# Signal_conditioning.net
KiCad netlist of a schematic drawn in Altium Designer
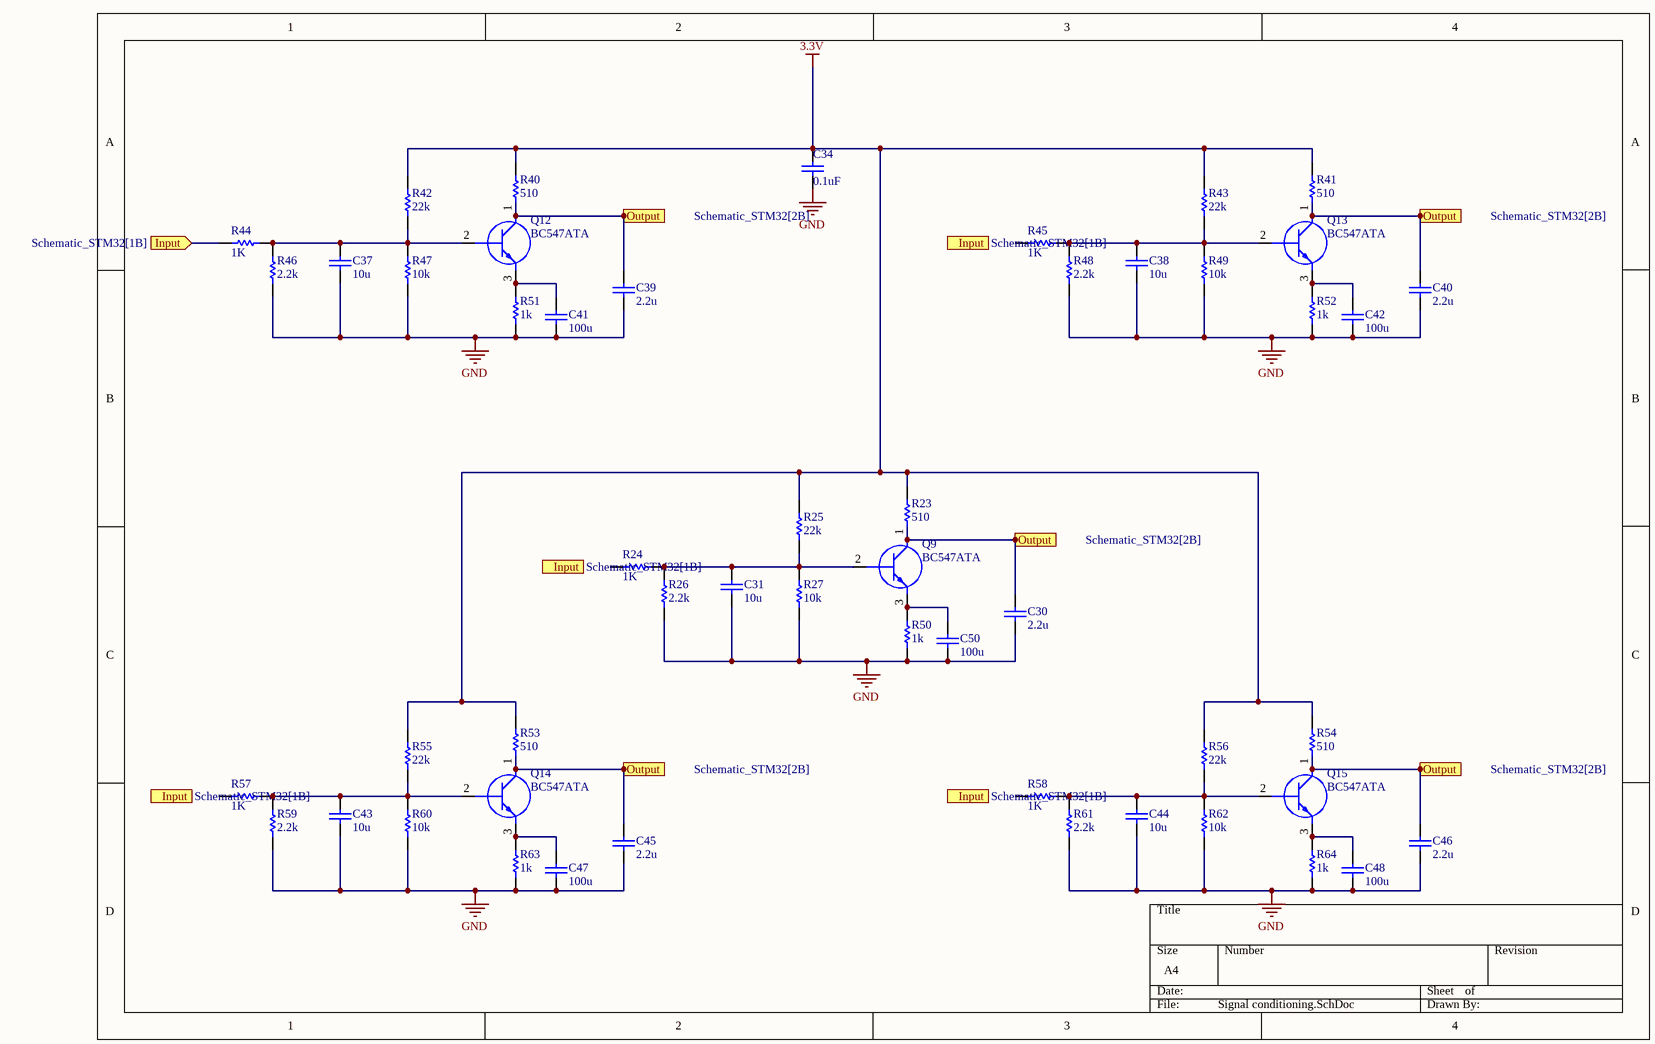
[diagram p0: Signal conditioning.SchDoc]

(export (version "E")
  (design (tool "Eeschema 10.0.6"))
  (components
    (comp (ref "C30")
      (value "2.2u")
      (description "Capacitor")
      (libsource (lib "Simulation Generic Components") (part "Capacitor"))
    )
    (comp (ref "C31")
      (value "10u")
      (description "Capacitor")
      (libsource (lib "Simulation Generic Components") (part "Capacitor"))
    )
    (comp (ref "C34")
      (value "0.1uF")
      (footprint "RAD-0.3")
      (description "Capacitor")
      (fields (field (name "Comment") "Cap") (field (name "PUBLISHER") "Altium Limited"))
      (libsource (lib "Miscellaneous Devices") (part "Cap"))
    )
    (comp (ref "C37")
      (value "10u")
      (description "Capacitor")
      (libsource (lib "Simulation Generic Components") (part "Capacitor"))
    )
    (comp (ref "C38")
      (value "10u")
      (description "Capacitor")
      (libsource (lib "Simulation Generic Components") (part "Capacitor"))
    )
    (comp (ref "C39")
      (value "2.2u")
      (description "Capacitor")
      (libsource (lib "Simulation Generic Components") (part "Capacitor"))
    )
    (comp (ref "C40")
      (value "2.2u")
      (description "Capacitor")
      (libsource (lib "Simulation Generic Components") (part "Capacitor"))
    )
    (comp (ref "C41")
      (value "100u")
      (description "Capacitor")
      (libsource (lib "Simulation Generic Components") (part "Capacitor"))
    )
    (comp (ref "C42")
      (value "100u")
      (description "Capacitor")
      (libsource (lib "Simulation Generic Components") (part "Capacitor"))
    )
    (comp (ref "C43")
      (value "10u")
      (description "Capacitor")
      (libsource (lib "Simulation Generic Components") (part "Capacitor"))
    )
    (comp (ref "C44")
      (value "10u")
      (description "Capacitor")
      (libsource (lib "Simulation Generic Components") (part "Capacitor"))
    )
    (comp (ref "C45")
      (value "2.2u")
      (description "Capacitor")
      (libsource (lib "Simulation Generic Components") (part "Capacitor"))
    )
    (comp (ref "C46")
      (value "2.2u")
      (description "Capacitor")
      (libsource (lib "Simulation Generic Components") (part "Capacitor"))
    )
    (comp (ref "C47")
      (value "100u")
      (description "Capacitor")
      (libsource (lib "Simulation Generic Components") (part "Capacitor"))
    )
    (comp (ref "C48")
      (value "100u")
      (description "Capacitor")
      (libsource (lib "Simulation Generic Components") (part "Capacitor"))
    )
    (comp (ref "C50")
      (value "100u")
      (description "Capacitor")
      (libsource (lib "Simulation Generic Components") (part "Capacitor"))
    )
    (comp (ref "Q9")
      (value "BC547ATA")
      (footprint "SamacSys:TO-92_(TO-226)")
      (description "Transistor BJT NPN")
      (fields (field (name "MOUSER PART NUMBER") "512-BC547ATA"))
      (libsource (lib "*") (part "BC547ATA"))
    )
    (comp (ref "Q12")
      (value "BC547ATA")
      (footprint "SamacSys:TO-92_(TO-226)")
      (description "Transistor BJT NPN")
      (fields (field (name "MOUSER PART NUMBER") "512-BC547ATA"))
      (libsource (lib "*") (part "BC547ATA"))
    )
    (comp (ref "Q13")
      (value "BC547ATA")
      (footprint "SamacSys:TO-92_(TO-226)")
      (description "Transistor BJT NPN")
      (fields (field (name "MOUSER PART NUMBER") "512-BC547ATA"))
      (libsource (lib "*") (part "BC547ATA"))
    )
    (comp (ref "Q14")
      (value "BC547ATA")
      (footprint "SamacSys:TO-92_(TO-226)")
      (description "Transistor BJT NPN")
      (fields (field (name "MOUSER PART NUMBER") "512-BC547ATA"))
      (libsource (lib "*") (part "BC547ATA"))
    )
    (comp (ref "Q15")
      (value "BC547ATA")
      (footprint "SamacSys:TO-92_(TO-226)")
      (description "Transistor BJT NPN")
      (fields (field (name "MOUSER PART NUMBER") "512-BC547ATA"))
      (libsource (lib "*") (part "BC547ATA"))
    )
    (comp (ref "R23")
      (value "510")
      (description "Resistor")
      (libsource (lib "Simulation Generic Components") (part "Resistor"))
    )
    (comp (ref "R24")
      (value "1K")
      (description "Resistor")
      (libsource (lib "Simulation Generic Components") (part "Resistor"))
    )
    (comp (ref "R25")
      (value "22k")
      (description "Resistor")
      (libsource (lib "Simulation Generic Components") (part "Resistor"))
    )
    (comp (ref "R26")
      (value "2.2k")
      (description "Resistor")
      (libsource (lib "Simulation Generic Components") (part "Resistor"))
    )
    (comp (ref "R27")
      (value "10k")
      (description "Resistor")
      (libsource (lib "Simulation Generic Components") (part "Resistor"))
    )
    (comp (ref "R40")
      (value "510")
      (description "Resistor")
      (libsource (lib "Simulation Generic Components") (part "Resistor"))
    )
    (comp (ref "R41")
      (value "510")
      (description "Resistor")
      (libsource (lib "Simulation Generic Components") (part "Resistor"))
    )
    (comp (ref "R42")
      (value "22k")
      (description "Resistor")
      (libsource (lib "Simulation Generic Components") (part "Resistor"))
    )
    (comp (ref "R43")
      (value "22k")
      (description "Resistor")
      (libsource (lib "Simulation Generic Components") (part "Resistor"))
    )
    (comp (ref "R44")
      (value "1K")
      (description "Resistor")
      (libsource (lib "Simulation Generic Components") (part "Resistor"))
    )
    (comp (ref "R45")
      (value "1K")
      (description "Resistor")
      (libsource (lib "Simulation Generic Components") (part "Resistor"))
    )
    (comp (ref "R46")
      (value "2.2k")
      (description "Resistor")
      (libsource (lib "Simulation Generic Components") (part "Resistor"))
    )
    (comp (ref "R47")
      (value "10k")
      (description "Resistor")
      (libsource (lib "Simulation Generic Components") (part "Resistor"))
    )
    (comp (ref "R48")
      (value "2.2k")
      (description "Resistor")
      (libsource (lib "Simulation Generic Components") (part "Resistor"))
    )
    (comp (ref "R49")
      (value "10k")
      (description "Resistor")
      (libsource (lib "Simulation Generic Components") (part "Resistor"))
    )
    (comp (ref "R50")
      (value "1k")
      (description "Resistor")
      (libsource (lib "Simulation Generic Components") (part "Resistor"))
    )
    (comp (ref "R51")
      (value "1k")
      (description "Resistor")
      (libsource (lib "Simulation Generic Components") (part "Resistor"))
    )
    (comp (ref "R52")
      (value "1k")
      (description "Resistor")
      (libsource (lib "Simulation Generic Components") (part "Resistor"))
    )
    (comp (ref "R53")
      (value "510")
      (description "Resistor")
      (libsource (lib "Simulation Generic Components") (part "Resistor"))
    )
    (comp (ref "R54")
      (value "510")
      (description "Resistor")
      (libsource (lib "Simulation Generic Components") (part "Resistor"))
    )
    (comp (ref "R55")
      (value "22k")
      (description "Resistor")
      (libsource (lib "Simulation Generic Components") (part "Resistor"))
    )
    (comp (ref "R56")
      (value "22k")
      (description "Resistor")
      (libsource (lib "Simulation Generic Components") (part "Resistor"))
    )
    (comp (ref "R57")
      (value "1K")
      (description "Resistor")
      (libsource (lib "Simulation Generic Components") (part "Resistor"))
    )
    (comp (ref "R58")
      (value "1K")
      (description "Resistor")
      (libsource (lib "Simulation Generic Components") (part "Resistor"))
    )
    (comp (ref "R59")
      (value "2.2k")
      (description "Resistor")
      (libsource (lib "Simulation Generic Components") (part "Resistor"))
    )
    (comp (ref "R60")
      (value "10k")
      (description "Resistor")
      (libsource (lib "Simulation Generic Components") (part "Resistor"))
    )
    (comp (ref "R61")
      (value "2.2k")
      (description "Resistor")
      (libsource (lib "Simulation Generic Components") (part "Resistor"))
    )
    (comp (ref "R62")
      (value "10k")
      (description "Resistor")
      (libsource (lib "Simulation Generic Components") (part "Resistor"))
    )
    (comp (ref "R63")
      (value "1k")
      (description "Resistor")
      (libsource (lib "Simulation Generic Components") (part "Resistor"))
    )
    (comp (ref "R64")
      (value "1k")
      (description "Resistor")
      (libsource (lib "Simulation Generic Components") (part "Resistor"))
    )
  )
  (nets
    (net (code "1") (name "/Input") (class "Default")
      (node (ref "R44") (pin "1") (pinfunction "1_1") (pintype "passive"))
    )
    (net (code "2") (name "/Output") (class "Default")
      (node (ref "C30") (pin "1") (pinfunction "1_1") (pintype "passive"))
      (node (ref "C39") (pin "1") (pinfunction "1_1") (pintype "passive"))
      (node (ref "C40") (pin "1") (pinfunction "1_1") (pintype "passive"))
      (node (ref "C45") (pin "1") (pinfunction "1_1") (pintype "passive"))
      (node (ref "C46") (pin "1") (pinfunction "1_1") (pintype "passive"))
      (node (ref "Q12") (pin "1") (pinfunction "C_1") (pintype "passive"))
      (node (ref "Q13") (pin "1") (pinfunction "C_1") (pintype "passive"))
      (node (ref "Q14") (pin "1") (pinfunction "C_1") (pintype "passive"))
      (node (ref "Q15") (pin "1") (pinfunction "C_1") (pintype "passive"))
      (node (ref "Q9") (pin "1") (pinfunction "C_1") (pintype "passive"))
      (node (ref "R23") (pin "1") (pinfunction "1_1") (pintype "passive"))
      (node (ref "R40") (pin "1") (pinfunction "1_1") (pintype "passive"))
      (node (ref "R41") (pin "1") (pinfunction "1_1") (pintype "passive"))
      (node (ref "R53") (pin "1") (pinfunction "1_1") (pintype "passive"))
      (node (ref "R54") (pin "1") (pinfunction "1_1") (pintype "passive"))
    )
    (net (code "3") (name "3.3V") (class "Default")
      (node (ref "C34") (pin "2") (pinfunction "2_2") (pintype "passive"))
      (node (ref "R23") (pin "2") (pinfunction "2_2") (pintype "passive"))
      (node (ref "R25") (pin "2") (pinfunction "2_2") (pintype "passive"))
      (node (ref "R40") (pin "2") (pinfunction "2_2") (pintype "passive"))
      (node (ref "R41") (pin "2") (pinfunction "2_2") (pintype "passive"))
      (node (ref "R42") (pin "2") (pinfunction "2_2") (pintype "passive"))
      (node (ref "R43") (pin "2") (pinfunction "2_2") (pintype "passive"))
      (node (ref "R53") (pin "2") (pinfunction "2_2") (pintype "passive"))
      (node (ref "R54") (pin "2") (pinfunction "2_2") (pintype "passive"))
      (node (ref "R55") (pin "2") (pinfunction "2_2") (pintype "passive"))
      (node (ref "R56") (pin "2") (pinfunction "2_2") (pintype "passive"))
    )
    (net (code "4") (name "GND") (class "Default")
      (node (ref "C30") (pin "2") (pinfunction "2_2") (pintype "passive"))
      (node (ref "C31") (pin "2") (pinfunction "2_2") (pintype "passive"))
      (node (ref "C34") (pin "1") (pinfunction "1_1") (pintype "passive"))
      (node (ref "C37") (pin "2") (pinfunction "2_2") (pintype "passive"))
      (node (ref "C38") (pin "2") (pinfunction "2_2") (pintype "passive"))
      (node (ref "C39") (pin "2") (pinfunction "2_2") (pintype "passive"))
      (node (ref "C40") (pin "2") (pinfunction "2_2") (pintype "passive"))
      (node (ref "C41") (pin "1") (pinfunction "1_1") (pintype "passive"))
      (node (ref "C42") (pin "1") (pinfunction "1_1") (pintype "passive"))
      (node (ref "C43") (pin "2") (pinfunction "2_2") (pintype "passive"))
      (node (ref "C44") (pin "2") (pinfunction "2_2") (pintype "passive"))
      (node (ref "C45") (pin "2") (pinfunction "2_2") (pintype "passive"))
      (node (ref "C46") (pin "2") (pinfunction "2_2") (pintype "passive"))
      (node (ref "C47") (pin "1") (pinfunction "1_1") (pintype "passive"))
      (node (ref "C48") (pin "1") (pinfunction "1_1") (pintype "passive"))
      (node (ref "C50") (pin "1") (pinfunction "1_1") (pintype "passive"))
      (node (ref "R26") (pin "1") (pinfunction "1_1") (pintype "passive"))
      (node (ref "R27") (pin "1") (pinfunction "1_1") (pintype "passive"))
      (node (ref "R46") (pin "1") (pinfunction "1_1") (pintype "passive"))
      (node (ref "R47") (pin "1") (pinfunction "1_1") (pintype "passive"))
      (node (ref "R48") (pin "1") (pinfunction "1_1") (pintype "passive"))
      (node (ref "R49") (pin "1") (pinfunction "1_1") (pintype "passive"))
      (node (ref "R50") (pin "1") (pinfunction "1_1") (pintype "passive"))
      (node (ref "R51") (pin "1") (pinfunction "1_1") (pintype "passive"))
      (node (ref "R52") (pin "1") (pinfunction "1_1") (pintype "passive"))
      (node (ref "R59") (pin "1") (pinfunction "1_1") (pintype "passive"))
      (node (ref "R60") (pin "1") (pinfunction "1_1") (pintype "passive"))
      (node (ref "R61") (pin "1") (pinfunction "1_1") (pintype "passive"))
      (node (ref "R62") (pin "1") (pinfunction "1_1") (pintype "passive"))
      (node (ref "R63") (pin "1") (pinfunction "1_1") (pintype "passive"))
      (node (ref "R64") (pin "1") (pinfunction "1_1") (pintype "passive"))
    )
    (net (code "5") (name "Net-(Q9-B)") (class "Default")
      (node (ref "C31") (pin "1") (pinfunction "1_1") (pintype "passive"))
      (node (ref "Q9") (pin "2") (pinfunction "B_2") (pintype "passive"))
      (node (ref "R24") (pin "2") (pinfunction "2_2") (pintype "passive"))
      (node (ref "R25") (pin "1") (pinfunction "1_1") (pintype "passive"))
      (node (ref "R26") (pin "2") (pinfunction "2_2") (pintype "passive"))
      (node (ref "R27") (pin "2") (pinfunction "2_2") (pintype "passive"))
    )
    (net (code "6") (name "Net-(Q9-E)") (class "Default")
      (node (ref "C50") (pin "2") (pinfunction "2_2") (pintype "passive"))
      (node (ref "Q9") (pin "3") (pinfunction "E_3") (pintype "passive"))
      (node (ref "R50") (pin "2") (pinfunction "2_2") (pintype "passive"))
    )
    (net (code "7") (name "Net-(Q12-B)") (class "Default")
      (node (ref "C37") (pin "1") (pinfunction "1_1") (pintype "passive"))
      (node (ref "Q12") (pin "2") (pinfunction "B_2") (pintype "passive"))
      (node (ref "R42") (pin "1") (pinfunction "1_1") (pintype "passive"))
      (node (ref "R44") (pin "2") (pinfunction "2_2") (pintype "passive"))
      (node (ref "R46") (pin "2") (pinfunction "2_2") (pintype "passive"))
      (node (ref "R47") (pin "2") (pinfunction "2_2") (pintype "passive"))
    )
    (net (code "8") (name "Net-(Q12-E)") (class "Default")
      (node (ref "C41") (pin "2") (pinfunction "2_2") (pintype "passive"))
      (node (ref "Q12") (pin "3") (pinfunction "E_3") (pintype "passive"))
      (node (ref "R51") (pin "2") (pinfunction "2_2") (pintype "passive"))
    )
    (net (code "9") (name "Net-(Q13-B)") (class "Default")
      (node (ref "C38") (pin "1") (pinfunction "1_1") (pintype "passive"))
      (node (ref "Q13") (pin "2") (pinfunction "B_2") (pintype "passive"))
      (node (ref "R43") (pin "1") (pinfunction "1_1") (pintype "passive"))
      (node (ref "R45") (pin "2") (pinfunction "2_2") (pintype "passive"))
      (node (ref "R48") (pin "2") (pinfunction "2_2") (pintype "passive"))
      (node (ref "R49") (pin "2") (pinfunction "2_2") (pintype "passive"))
    )
    (net (code "10") (name "Net-(Q13-E)") (class "Default")
      (node (ref "C42") (pin "2") (pinfunction "2_2") (pintype "passive"))
      (node (ref "Q13") (pin "3") (pinfunction "E_3") (pintype "passive"))
      (node (ref "R52") (pin "2") (pinfunction "2_2") (pintype "passive"))
    )
    (net (code "11") (name "Net-(Q14-B)") (class "Default")
      (node (ref "C43") (pin "1") (pinfunction "1_1") (pintype "passive"))
      (node (ref "Q14") (pin "2") (pinfunction "B_2") (pintype "passive"))
      (node (ref "R55") (pin "1") (pinfunction "1_1") (pintype "passive"))
      (node (ref "R57") (pin "2") (pinfunction "2_2") (pintype "passive"))
      (node (ref "R59") (pin "2") (pinfunction "2_2") (pintype "passive"))
      (node (ref "R60") (pin "2") (pinfunction "2_2") (pintype "passive"))
    )
    (net (code "12") (name "Net-(Q14-E)") (class "Default")
      (node (ref "C47") (pin "2") (pinfunction "2_2") (pintype "passive"))
      (node (ref "Q14") (pin "3") (pinfunction "E_3") (pintype "passive"))
      (node (ref "R63") (pin "2") (pinfunction "2_2") (pintype "passive"))
    )
    (net (code "13") (name "Net-(Q15-B)") (class "Default")
      (node (ref "C44") (pin "1") (pinfunction "1_1") (pintype "passive"))
      (node (ref "Q15") (pin "2") (pinfunction "B_2") (pintype "passive"))
      (node (ref "R56") (pin "1") (pinfunction "1_1") (pintype "passive"))
      (node (ref "R58") (pin "2") (pinfunction "2_2") (pintype "passive"))
      (node (ref "R61") (pin "2") (pinfunction "2_2") (pintype "passive"))
      (node (ref "R62") (pin "2") (pinfunction "2_2") (pintype "passive"))
    )
    (net (code "14") (name "Net-(Q15-E)") (class "Default")
      (node (ref "C48") (pin "2") (pinfunction "2_2") (pintype "passive"))
      (node (ref "Q15") (pin "3") (pinfunction "E_3") (pintype "passive"))
      (node (ref "R64") (pin "2") (pinfunction "2_2") (pintype "passive"))
    )
    (net (code "15") (name "unconnected-(R24-Pad1)") (class "Default")
      (node (ref "R24") (pin "1") (pinfunction "1_1") (pintype "passive"))
    )
    (net (code "16") (name "unconnected-(R45-Pad1)") (class "Default")
      (node (ref "R45") (pin "1") (pinfunction "1_1") (pintype "passive"))
    )
    (net (code "17") (name "unconnected-(R57-Pad1)") (class "Default")
      (node (ref "R57") (pin "1") (pinfunction "1_1") (pintype "passive"))
    )
    (net (code "18") (name "unconnected-(R58-Pad1)") (class "Default")
      (node (ref "R58") (pin "1") (pinfunction "1_1") (pintype "passive"))
    )
  )
)
